# mgt_breakout.net
KiCad netlist of a schematic drawn in Altium Designer
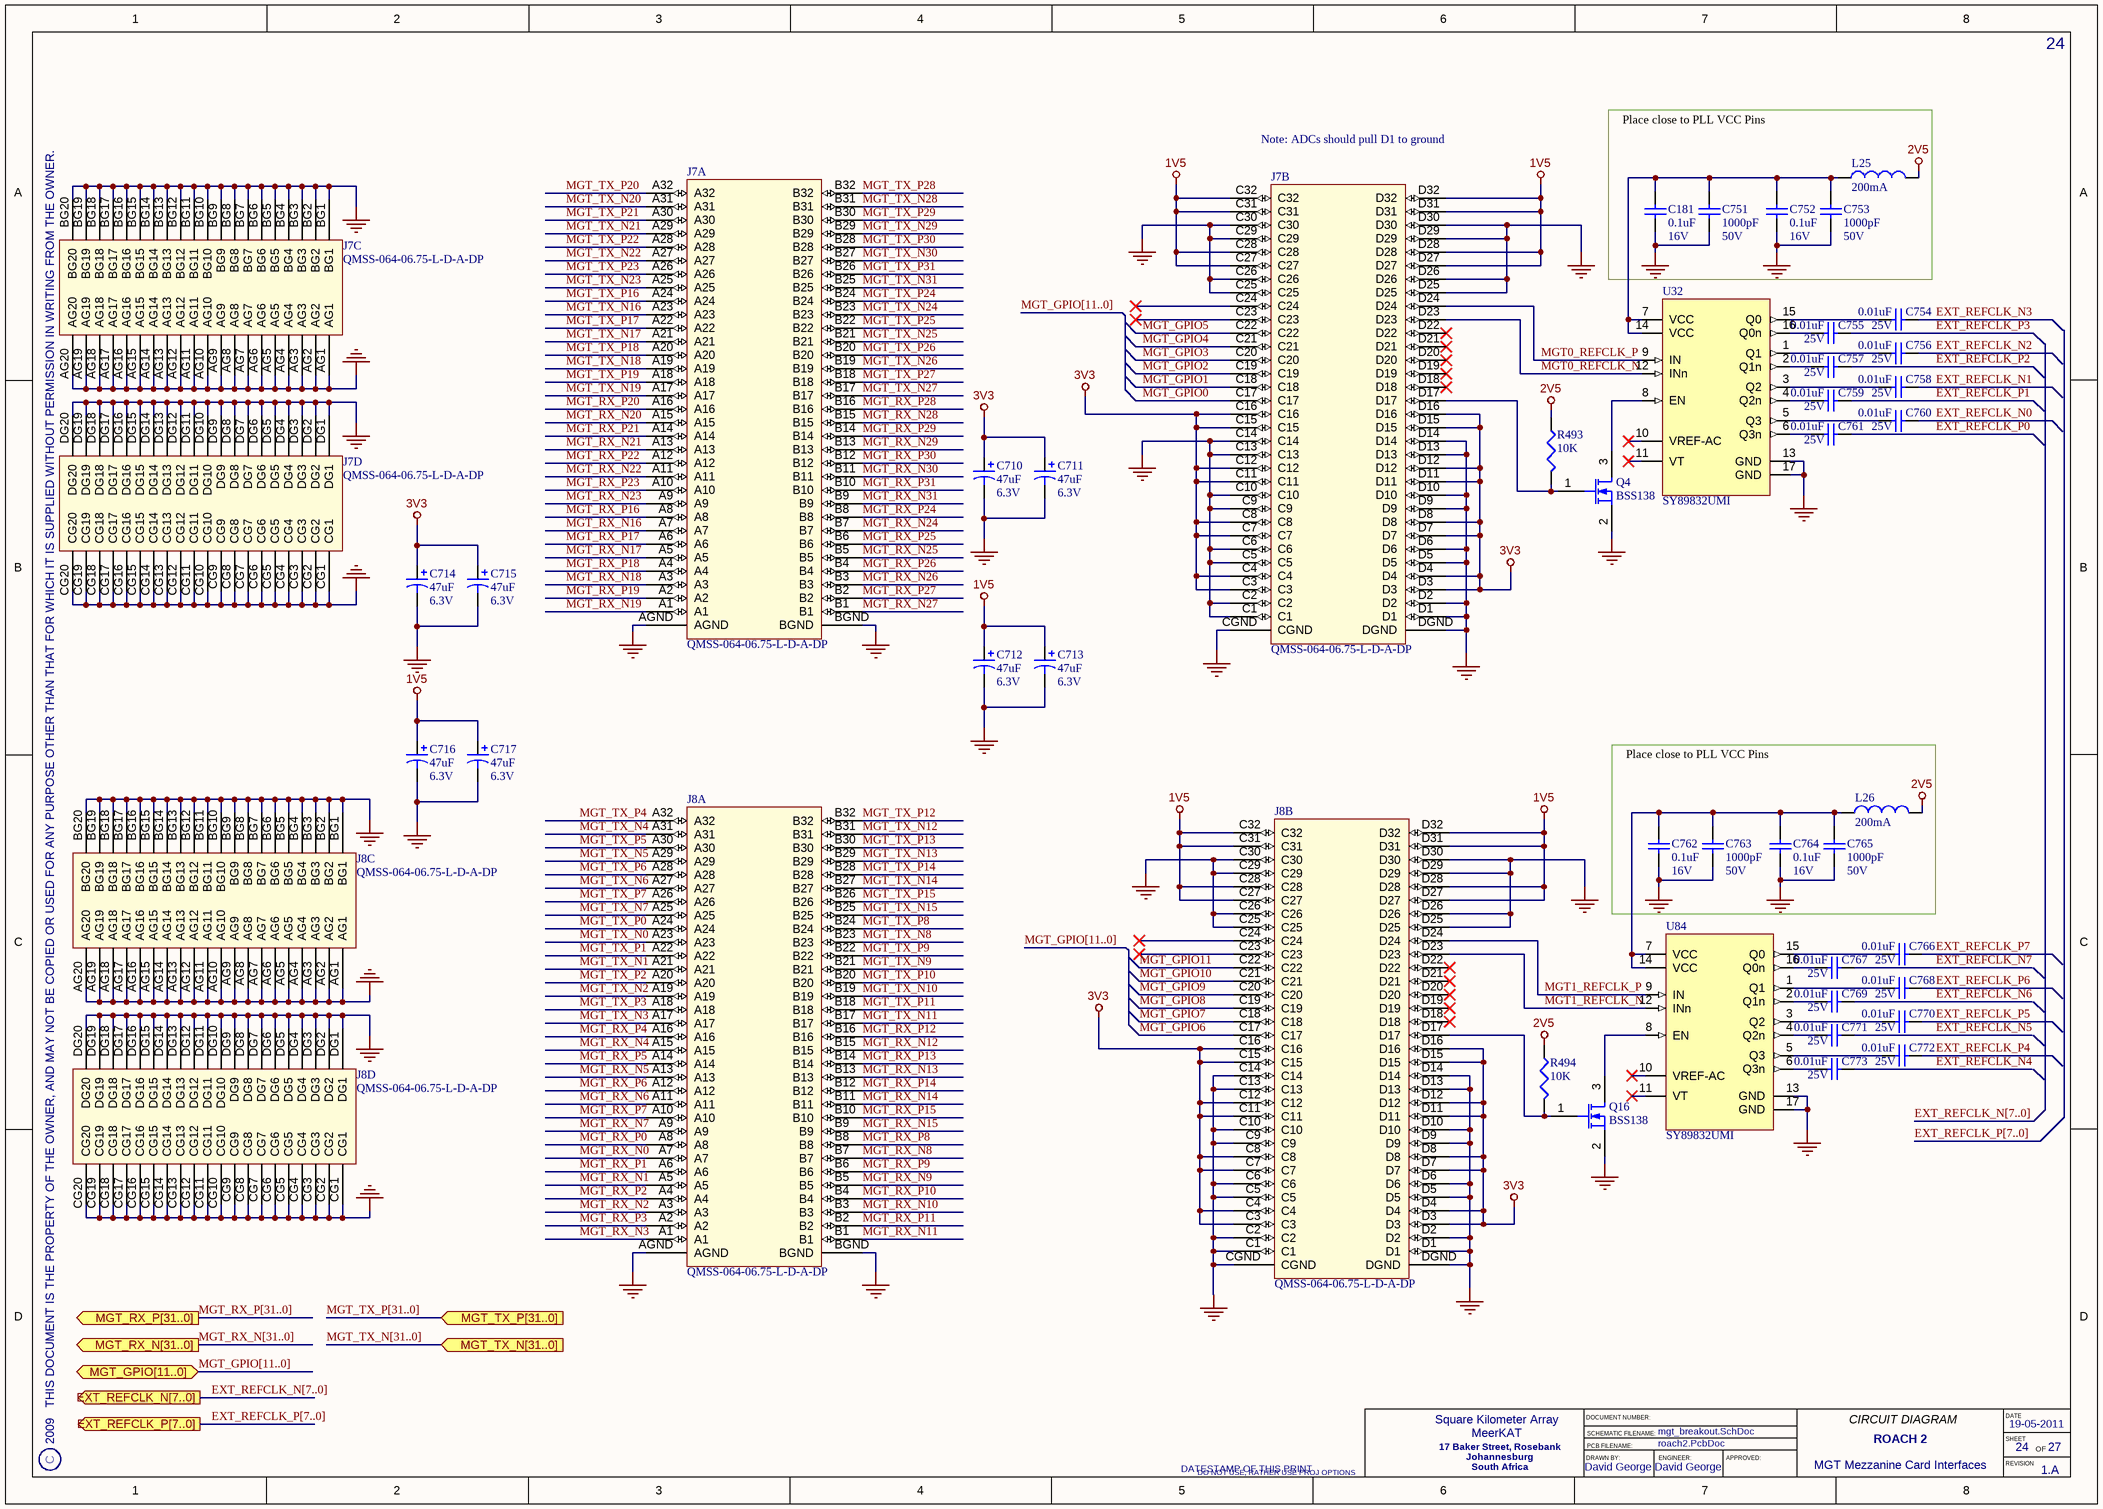
[diagram p0: mgt_breakout.SchDoc]

(export (version "E")
  (design (tool "Eeschema 10.0.6"))
  (components
    (comp (ref "C181")
      (value "0.1uF")
      (footprint "CAPC1005X60L")
      (description "0.1uF, Ceramic Capacitor")
      (fields
        (field (name "RATING") "16V")
        (field (name "MANUFACTURER") "VENKEL")
        (field (name "PARTNUM") "C0402X7R160-104KN")
      )
      (libsource (lib "altium_db") (part "CapStd"))
    )
    (comp (ref "C710")
      (value "47uF")
      (footprint "CAPMP3528X120L")
      (description "47uF, Conductive Polymer Chip Capacitor")
      (fields
        (field (name "RATING") "6.3V")
        (field (name "MANUFACTURER") "KEMET")
        (field (name "PARTNUM") "T520T476M006ATE070")
      )
      (libsource (lib "altium_db") (part "CapPol"))
    )
    (comp (ref "C711")
      (value "47uF")
      (footprint "CAPMP3528X120L")
      (description "47uF, Conductive Polymer Chip Capacitor")
      (fields
        (field (name "RATING") "6.3V")
        (field (name "MANUFACTURER") "KEMET")
        (field (name "PARTNUM") "T520T476M006ATE070")
      )
      (libsource (lib "altium_db") (part "CapPol"))
    )
    (comp (ref "C712")
      (value "47uF")
      (footprint "CAPMP3528X120L")
      (description "47uF, Conductive Polymer Chip Capacitor")
      (fields
        (field (name "RATING") "6.3V")
        (field (name "MANUFACTURER") "KEMET")
        (field (name "PARTNUM") "T520T476M006ATE070")
      )
      (libsource (lib "altium_db") (part "CapPol"))
    )
    (comp (ref "C713")
      (value "47uF")
      (footprint "CAPMP3528X120L")
      (description "47uF, Conductive Polymer Chip Capacitor")
      (fields
        (field (name "RATING") "6.3V")
        (field (name "MANUFACTURER") "KEMET")
        (field (name "PARTNUM") "T520T476M006ATE070")
      )
      (libsource (lib "altium_db") (part "CapPol"))
    )
    (comp (ref "C714")
      (value "47uF")
      (footprint "CAPMP3528X120L")
      (description "47uF, Conductive Polymer Chip Capacitor")
      (fields
        (field (name "RATING") "6.3V")
        (field (name "MANUFACTURER") "KEMET")
        (field (name "PARTNUM") "T520T476M006ATE070")
      )
      (libsource (lib "altium_db") (part "CapPol"))
    )
    (comp (ref "C715")
      (value "47uF")
      (footprint "CAPMP3528X120L")
      (description "47uF, Conductive Polymer Chip Capacitor")
      (fields
        (field (name "RATING") "6.3V")
        (field (name "MANUFACTURER") "KEMET")
        (field (name "PARTNUM") "T520T476M006ATE070")
      )
      (libsource (lib "altium_db") (part "CapPol"))
    )
    (comp (ref "C716")
      (value "47uF")
      (footprint "CAPMP3528X120L")
      (description "47uF, Conductive Polymer Chip Capacitor")
      (fields
        (field (name "RATING") "6.3V")
        (field (name "MANUFACTURER") "KEMET")
        (field (name "PARTNUM") "T520T476M006ATE070")
      )
      (libsource (lib "altium_db") (part "CapPol"))
    )
    (comp (ref "C717")
      (value "47uF")
      (footprint "CAPMP3528X120L")
      (description "47uF, Conductive Polymer Chip Capacitor")
      (fields
        (field (name "RATING") "6.3V")
        (field (name "MANUFACTURER") "KEMET")
        (field (name "PARTNUM") "T520T476M006ATE070")
      )
      (libsource (lib "altium_db") (part "CapPol"))
    )
    (comp (ref "C751")
      (value "1000pF")
      (footprint "CAPC1005X55L")
      (description "1000pF, Ceramic Capacitor")
      (fields
        (field (name "RATING") "50V")
        (field (name "MANUFACTURER") "MURATA")
        (field (name "PARTNUM") "GRM155R61H102KA01D")
      )
      (libsource (lib "altium_db") (part "CapStd"))
    )
    (comp (ref "C752")
      (value "0.1uF")
      (footprint "CAPC1005X60L")
      (description "0.1uF, Ceramic Capacitor")
      (fields
        (field (name "RATING") "16V")
        (field (name "MANUFACTURER") "VENKEL")
        (field (name "PARTNUM") "C0402X7R160-104KN")
      )
      (libsource (lib "altium_db") (part "CapStd"))
    )
    (comp (ref "C753")
      (value "1000pF")
      (footprint "CAPC1005X55L")
      (description "1000pF, Ceramic Capacitor")
      (fields
        (field (name "RATING") "50V")
        (field (name "MANUFACTURER") "MURATA")
        (field (name "PARTNUM") "GRM155R61H102KA01D")
      )
      (libsource (lib "altium_db") (part "CapStd"))
    )
    (comp (ref "C754")
      (value "0.01uF")
      (footprint "CAPC1005X55L")
      (description "0.01uF, Ceramic Capacitor")
      (fields
        (field (name "RATING") "25V")
        (field (name "MANUFACTURER") "MURATA")
        (field (name "PARTNUM") "GRM155R71E103KA01D")
      )
      (libsource (lib "altium_db") (part "CapStd"))
    )
    (comp (ref "C755")
      (value "0.01uF")
      (footprint "CAPC1005X55L")
      (description "0.01uF, Ceramic Capacitor")
      (fields
        (field (name "RATING") "25V")
        (field (name "MANUFACTURER") "MURATA")
        (field (name "PARTNUM") "GRM155R71E103KA01D")
      )
      (libsource (lib "altium_db") (part "CapStd"))
    )
    (comp (ref "C756")
      (value "0.01uF")
      (footprint "CAPC1005X55L")
      (description "0.01uF, Ceramic Capacitor")
      (fields
        (field (name "RATING") "25V")
        (field (name "MANUFACTURER") "MURATA")
        (field (name "PARTNUM") "GRM155R71E103KA01D")
      )
      (libsource (lib "altium_db") (part "CapStd"))
    )
    (comp (ref "C757")
      (value "0.01uF")
      (footprint "CAPC1005X55L")
      (description "0.01uF, Ceramic Capacitor")
      (fields
        (field (name "RATING") "25V")
        (field (name "MANUFACTURER") "MURATA")
        (field (name "PARTNUM") "GRM155R71E103KA01D")
      )
      (libsource (lib "altium_db") (part "CapStd"))
    )
    (comp (ref "C758")
      (value "0.01uF")
      (footprint "CAPC1005X55L")
      (description "0.01uF, Ceramic Capacitor")
      (fields
        (field (name "RATING") "25V")
        (field (name "MANUFACTURER") "MURATA")
        (field (name "PARTNUM") "GRM155R71E103KA01D")
      )
      (libsource (lib "altium_db") (part "CapStd"))
    )
    (comp (ref "C759")
      (value "0.01uF")
      (footprint "CAPC1005X55L")
      (description "0.01uF, Ceramic Capacitor")
      (fields
        (field (name "RATING") "25V")
        (field (name "MANUFACTURER") "MURATA")
        (field (name "PARTNUM") "GRM155R71E103KA01D")
      )
      (libsource (lib "altium_db") (part "CapStd"))
    )
    (comp (ref "C760")
      (value "0.01uF")
      (footprint "CAPC1005X55L")
      (description "0.01uF, Ceramic Capacitor")
      (fields
        (field (name "RATING") "25V")
        (field (name "MANUFACTURER") "MURATA")
        (field (name "PARTNUM") "GRM155R71E103KA01D")
      )
      (libsource (lib "altium_db") (part "CapStd"))
    )
    (comp (ref "C761")
      (value "0.01uF")
      (footprint "CAPC1005X55L")
      (description "0.01uF, Ceramic Capacitor")
      (fields
        (field (name "RATING") "25V")
        (field (name "MANUFACTURER") "MURATA")
        (field (name "PARTNUM") "GRM155R71E103KA01D")
      )
      (libsource (lib "altium_db") (part "CapStd"))
    )
    (comp (ref "C762")
      (value "0.1uF")
      (footprint "CAPC1005X60L")
      (description "0.1uF, Ceramic Capacitor")
      (fields
        (field (name "RATING") "16V")
        (field (name "MANUFACTURER") "VENKEL")
        (field (name "PARTNUM") "C0402X7R160-104KN")
      )
      (libsource (lib "altium_db") (part "CapStd"))
    )
    (comp (ref "C763")
      (value "1000pF")
      (footprint "CAPC1005X55L")
      (description "1000pF, Ceramic Capacitor")
      (fields
        (field (name "RATING") "50V")
        (field (name "MANUFACTURER") "MURATA")
        (field (name "PARTNUM") "GRM155R61H102KA01D")
      )
      (libsource (lib "altium_db") (part "CapStd"))
    )
    (comp (ref "C764")
      (value "0.1uF")
      (footprint "CAPC1005X60L")
      (description "0.1uF, Ceramic Capacitor")
      (fields
        (field (name "RATING") "16V")
        (field (name "MANUFACTURER") "VENKEL")
        (field (name "PARTNUM") "C0402X7R160-104KN")
      )
      (libsource (lib "altium_db") (part "CapStd"))
    )
    (comp (ref "C765")
      (value "1000pF")
      (footprint "CAPC1005X55L")
      (description "1000pF, Ceramic Capacitor")
      (fields
        (field (name "RATING") "50V")
        (field (name "MANUFACTURER") "MURATA")
        (field (name "PARTNUM") "GRM155R61H102KA01D")
      )
      (libsource (lib "altium_db") (part "CapStd"))
    )
    (comp (ref "C766")
      (value "0.01uF")
      (footprint "CAPC1005X55L")
      (description "0.01uF, Ceramic Capacitor")
      (fields
        (field (name "RATING") "25V")
        (field (name "MANUFACTURER") "MURATA")
        (field (name "PARTNUM") "GRM155R71E103KA01D")
      )
      (libsource (lib "altium_db") (part "CapStd"))
    )
    (comp (ref "C767")
      (value "0.01uF")
      (footprint "CAPC1005X55L")
      (description "0.01uF, Ceramic Capacitor")
      (fields
        (field (name "RATING") "25V")
        (field (name "MANUFACTURER") "MURATA")
        (field (name "PARTNUM") "GRM155R71E103KA01D")
      )
      (libsource (lib "altium_db") (part "CapStd"))
    )
    (comp (ref "C768")
      (value "0.01uF")
      (footprint "CAPC1005X55L")
      (description "0.01uF, Ceramic Capacitor")
      (fields
        (field (name "RATING") "25V")
        (field (name "MANUFACTURER") "MURATA")
        (field (name "PARTNUM") "GRM155R71E103KA01D")
      )
      (libsource (lib "altium_db") (part "CapStd"))
    )
    (comp (ref "C769")
      (value "0.01uF")
      (footprint "CAPC1005X55L")
      (description "0.01uF, Ceramic Capacitor")
      (fields
        (field (name "RATING") "25V")
        (field (name "MANUFACTURER") "MURATA")
        (field (name "PARTNUM") "GRM155R71E103KA01D")
      )
      (libsource (lib "altium_db") (part "CapStd"))
    )
    (comp (ref "C770")
      (value "0.01uF")
      (footprint "CAPC1005X55L")
      (description "0.01uF, Ceramic Capacitor")
      (fields
        (field (name "RATING") "25V")
        (field (name "MANUFACTURER") "MURATA")
        (field (name "PARTNUM") "GRM155R71E103KA01D")
      )
      (libsource (lib "altium_db") (part "CapStd"))
    )
    (comp (ref "C771")
      (value "0.01uF")
      (footprint "CAPC1005X55L")
      (description "0.01uF, Ceramic Capacitor")
      (fields
        (field (name "RATING") "25V")
        (field (name "MANUFACTURER") "MURATA")
        (field (name "PARTNUM") "GRM155R71E103KA01D")
      )
      (libsource (lib "altium_db") (part "CapStd"))
    )
    (comp (ref "C772")
      (value "0.01uF")
      (footprint "CAPC1005X55L")
      (description "0.01uF, Ceramic Capacitor")
      (fields
        (field (name "RATING") "25V")
        (field (name "MANUFACTURER") "MURATA")
        (field (name "PARTNUM") "GRM155R71E103KA01D")
      )
      (libsource (lib "altium_db") (part "CapStd"))
    )
    (comp (ref "C773")
      (value "0.01uF")
      (footprint "CAPC1005X55L")
      (description "0.01uF, Ceramic Capacitor")
      (fields
        (field (name "RATING") "25V")
        (field (name "MANUFACTURER") "MURATA")
        (field (name "PARTNUM") "GRM155R71E103KA01D")
      )
      (libsource (lib "altium_db") (part "CapStd"))
    )
    (comp (ref "J7")
      (value "QMSS-064-06_75-L-D-A-DP")
      (footprint "SAMTEC_QMSS-064-06_75-L-D-A-DP")
      (description "Shielded, 64-Differential Pair, Rugged High-Speed Terminal Strip, 0.635mm Pitch,")
      (fields (field (name "PARTNUM") "QMSS-064-06.75-L-D-A-DP"))
      (libsource (lib "altium_db") (part "QMSS-064-06_75-L-D-A-DP"))
    )
    (comp (ref "J8")
      (value "QMSS-064-06_75-L-D-A-DP")
      (footprint "SAMTEC_QMSS-064-06_75-L-D-A-DP")
      (description "Shielded, 64-Differential Pair, Rugged High-Speed Terminal Strip, 0.635mm Pitch,")
      (fields (field (name "PARTNUM") "QMSS-064-06.75-L-D-A-DP"))
      (libsource (lib "altium_db") (part "QMSS-064-06_75-L-D-A-DP"))
    )
    (comp (ref "L25")
      (value "600R")
      (footprint "INDC2012X130L")
      (description "600 Ohm, Chip Ferrite Bead")
      (fields
        (field (name "RATING") "200mA")
        (field (name "MANUFACTURER") "Murata")
        (field (name "PARTNUM") "BLM21BD601SN1")
      )
      (libsource (lib "altium_db") (part "IndStd"))
    )
    (comp (ref "L26")
      (value "600R")
      (footprint "INDC2012X130L")
      (description "600 Ohm, Chip Ferrite Bead")
      (fields
        (field (name "RATING") "200mA")
        (field (name "MANUFACTURER") "Murata")
        (field (name "PARTNUM") "BLM21BD601SN1")
      )
      (libsource (lib "altium_db") (part "IndStd"))
    )
    (comp (ref "Q4")
      (value "BSS138")
      (footprint "SOT95P245X110-3N")
      (description "N-Channel Logic Level Enhancement Mode Field Effect Transistor")
      (fields (field (name "MANUFACTURER") "Fairchild Semiconductor"))
      (libsource (lib "altium_db") (part "BSS138"))
    )
    (comp (ref "Q16")
      (value "BSS138")
      (footprint "SOT95P245X110-3N")
      (description "N-Channel Logic Level Enhancement Mode Field Effect Transistor")
      (fields (field (name "MANUFACTURER") "Fairchild Semiconductor"))
      (libsource (lib "altium_db") (part "BSS138"))
    )
    (comp (ref "R493")
      (value "10K")
      (footprint "RESC1005X40L")
      (description "10K, 1.1mm x 0.5mm, Thick Film Resistor")
      (fields (field (name "MANUFACTURER") "ROYALOHM") (field (name "PARTNUM") "0402WGJ0103T1E"))
      (libsource (lib "altium_db") (part "ResStd"))
    )
    (comp (ref "R494")
      (value "10K")
      (footprint "RESC1005X40L")
      (description "10K, 1.1mm x 0.5mm, Thick Film Resistor")
      (fields (field (name "MANUFACTURER") "ROYALOHM") (field (name "PARTNUM") "0402WGJ0103T1E"))
      (libsource (lib "altium_db") (part "ResStd"))
    )
    (comp (ref "U32")
      (value "SY89832UMI")
      (footprint "MLF-16")
      (description "2.5 C Ultra-precision 1:4 LVDS Fanout Buffer/Translator with Interal Termination")
      (fields (field (name "MANUFACTURER") "Micrel"))
      (libsource (lib "altium_db") (part "SY89832UMI"))
    )
    (comp (ref "U84")
      (value "SY89832UMI")
      (footprint "MLF-16")
      (description "2.5 C Ultra-precision 1:4 LVDS Fanout Buffer/Translator with Interal Termination")
      (fields (field (name "MANUFACTURER") "Micrel"))
      (libsource (lib "altium_db") (part "SY89832UMI"))
    )
  )
  (nets
    (net (code "1") (name "/EXT_REFCLK_N0") (class "Default")
      (node (ref "C760") (pin "2") (pinfunction "2_2") (pintype "passive"))
    )
    (net (code "2") (name "/EXT_REFCLK_N1") (class "Default")
      (node (ref "C758") (pin "2") (pinfunction "2_2") (pintype "passive"))
    )
    (net (code "3") (name "/EXT_REFCLK_N2") (class "Default")
      (node (ref "C756") (pin "2") (pinfunction "2_2") (pintype "passive"))
    )
    (net (code "4") (name "/EXT_REFCLK_N3") (class "Default")
      (node (ref "C754") (pin "2") (pinfunction "2_2") (pintype "passive"))
    )
    (net (code "5") (name "/EXT_REFCLK_N4") (class "Default")
      (node (ref "C773") (pin "2") (pinfunction "2_2") (pintype "passive"))
    )
    (net (code "6") (name "/EXT_REFCLK_N5") (class "Default")
      (node (ref "C771") (pin "2") (pinfunction "2_2") (pintype "passive"))
    )
    (net (code "7") (name "/EXT_REFCLK_N6") (class "Default")
      (node (ref "C769") (pin "2") (pinfunction "2_2") (pintype "passive"))
    )
    (net (code "8") (name "/EXT_REFCLK_N7") (class "Default")
      (node (ref "C767") (pin "2") (pinfunction "2_2") (pintype "passive"))
    )
    (net (code "10") (name "/EXT_REFCLK_P0") (class "Default")
      (node (ref "C761") (pin "2") (pinfunction "2_2") (pintype "passive"))
    )
    (net (code "11") (name "/EXT_REFCLK_P1") (class "Default")
      (node (ref "C759") (pin "2") (pinfunction "2_2") (pintype "passive"))
    )
    (net (code "12") (name "/EXT_REFCLK_P2") (class "Default")
      (node (ref "C757") (pin "2") (pinfunction "2_2") (pintype "passive"))
    )
    (net (code "13") (name "/EXT_REFCLK_P3") (class "Default")
      (node (ref "C755") (pin "2") (pinfunction "2_2") (pintype "passive"))
    )
    (net (code "14") (name "/EXT_REFCLK_P4") (class "Default")
      (node (ref "C772") (pin "2") (pinfunction "2_2") (pintype "passive"))
    )
    (net (code "15") (name "/EXT_REFCLK_P5") (class "Default")
      (node (ref "C770") (pin "2") (pinfunction "2_2") (pintype "passive"))
    )
    (net (code "16") (name "/EXT_REFCLK_P6") (class "Default")
      (node (ref "C768") (pin "2") (pinfunction "2_2") (pintype "passive"))
    )
    (net (code "17") (name "/EXT_REFCLK_P7") (class "Default")
      (node (ref "C766") (pin "2") (pinfunction "2_2") (pintype "passive"))
    )
    (net (code "19") (name "/MGT0_REFCLK_N") (class "Default")
      (node (ref "J7") (pin "D23") (pinfunction "D23_D23") (pintype "bidirectional"))
      (node (ref "U32") (pin "12") (pinfunction "INn_12") (pintype "input"))
    )
    (net (code "20") (name "/MGT0_REFCLK_P") (class "Default")
      (node (ref "J7") (pin "D24") (pinfunction "D24_D24") (pintype "bidirectional"))
      (node (ref "U32") (pin "9") (pinfunction "IN_9") (pintype "input"))
    )
    (net (code "21") (name "/MGT1_REFCLK_N") (class "Default")
      (node (ref "J8") (pin "D23") (pinfunction "D23_D23") (pintype "bidirectional"))
      (node (ref "U84") (pin "12") (pinfunction "INn_12") (pintype "input"))
    )
    (net (code "22") (name "/MGT1_REFCLK_P") (class "Default")
      (node (ref "J8") (pin "D24") (pinfunction "D24_D24") (pintype "bidirectional"))
      (node (ref "U84") (pin "9") (pinfunction "IN_9") (pintype "input"))
    )
    (net (code "23") (name "/MGT_GPIO0") (class "Default")
      (node (ref "J7") (pin "C17") (pinfunction "C17_C17") (pintype "bidirectional"))
    )
    (net (code "24") (name "/MGT_GPIO1") (class "Default")
      (node (ref "J7") (pin "C18") (pinfunction "C18_C18") (pintype "bidirectional"))
    )
    (net (code "25") (name "/MGT_GPIO2") (class "Default")
      (node (ref "J7") (pin "C19") (pinfunction "C19_C19") (pintype "bidirectional"))
    )
    (net (code "26") (name "/MGT_GPIO3") (class "Default")
      (node (ref "J7") (pin "C20") (pinfunction "C20_C20") (pintype "bidirectional"))
    )
    (net (code "27") (name "/MGT_GPIO4") (class "Default")
      (node (ref "J7") (pin "C21") (pinfunction "C21_C21") (pintype "bidirectional"))
    )
    (net (code "28") (name "/MGT_GPIO5") (class "Default")
      (node (ref "J7") (pin "C22") (pinfunction "C22_C22") (pintype "bidirectional"))
    )
    (net (code "29") (name "/MGT_GPIO6") (class "Default")
      (node (ref "J8") (pin "C17") (pinfunction "C17_C17") (pintype "bidirectional"))
    )
    (net (code "30") (name "/MGT_GPIO7") (class "Default")
      (node (ref "J8") (pin "C18") (pinfunction "C18_C18") (pintype "bidirectional"))
    )
    (net (code "31") (name "/MGT_GPIO8") (class "Default")
      (node (ref "J8") (pin "C19") (pinfunction "C19_C19") (pintype "bidirectional"))
    )
    (net (code "32") (name "/MGT_GPIO9") (class "Default")
      (node (ref "J8") (pin "C20") (pinfunction "C20_C20") (pintype "bidirectional"))
    )
    (net (code "33") (name "/MGT_GPIO10") (class "Default")
      (node (ref "J8") (pin "C21") (pinfunction "C21_C21") (pintype "bidirectional"))
    )
    (net (code "34") (name "/MGT_GPIO11") (class "Default")
      (node (ref "J8") (pin "C22") (pinfunction "C22_C22") (pintype "bidirectional"))
    )
    (net (code "36") (name "/MGT_RX_N0") (class "Default")
      (node (ref "J8") (pin "A7") (pinfunction "A7_A7") (pintype "bidirectional"))
    )
    (net (code "37") (name "/MGT_RX_N1") (class "Default")
      (node (ref "J8") (pin "A5") (pinfunction "A5_A5") (pintype "bidirectional"))
    )
    (net (code "38") (name "/MGT_RX_N2") (class "Default")
      (node (ref "J8") (pin "A3") (pinfunction "A3_A3") (pintype "bidirectional"))
    )
    (net (code "39") (name "/MGT_RX_N3") (class "Default")
      (node (ref "J8") (pin "A1") (pinfunction "A1_A1") (pintype "bidirectional"))
    )
    (net (code "40") (name "/MGT_RX_N4") (class "Default")
      (node (ref "J8") (pin "A15") (pinfunction "A15_A15") (pintype "bidirectional"))
    )
    (net (code "41") (name "/MGT_RX_N5") (class "Default")
      (node (ref "J8") (pin "A13") (pinfunction "A13_A13") (pintype "bidirectional"))
    )
    (net (code "42") (name "/MGT_RX_N6") (class "Default")
      (node (ref "J8") (pin "A11") (pinfunction "A11_A11") (pintype "bidirectional"))
    )
    (net (code "43") (name "/MGT_RX_N7") (class "Default")
      (node (ref "J8") (pin "A9") (pinfunction "A9_A9") (pintype "bidirectional"))
    )
    (net (code "44") (name "/MGT_RX_N8") (class "Default")
      (node (ref "J8") (pin "B7") (pinfunction "B7_B7") (pintype "bidirectional"))
    )
    (net (code "45") (name "/MGT_RX_N9") (class "Default")
      (node (ref "J8") (pin "B5") (pinfunction "B5_B5") (pintype "bidirectional"))
    )
    (net (code "46") (name "/MGT_RX_N10") (class "Default")
      (node (ref "J8") (pin "B3") (pinfunction "B3_B3") (pintype "bidirectional"))
    )
    (net (code "47") (name "/MGT_RX_N11") (class "Default")
      (node (ref "J8") (pin "B1") (pinfunction "B1_B1") (pintype "bidirectional"))
    )
    (net (code "48") (name "/MGT_RX_N12") (class "Default")
      (node (ref "J8") (pin "B15") (pinfunction "B15_B15") (pintype "bidirectional"))
    )
    (net (code "49") (name "/MGT_RX_N13") (class "Default")
      (node (ref "J8") (pin "B13") (pinfunction "B13_B13") (pintype "bidirectional"))
    )
    (net (code "50") (name "/MGT_RX_N14") (class "Default")
      (node (ref "J8") (pin "B11") (pinfunction "B11_B11") (pintype "bidirectional"))
    )
    (net (code "51") (name "/MGT_RX_N15") (class "Default")
      (node (ref "J8") (pin "B9") (pinfunction "B9_B9") (pintype "bidirectional"))
    )
    (net (code "52") (name "/MGT_RX_N16") (class "Default")
      (node (ref "J7") (pin "A7") (pinfunction "A7_A7") (pintype "bidirectional"))
    )
    (net (code "53") (name "/MGT_RX_N17") (class "Default")
      (node (ref "J7") (pin "A5") (pinfunction "A5_A5") (pintype "bidirectional"))
    )
    (net (code "54") (name "/MGT_RX_N18") (class "Default")
      (node (ref "J7") (pin "A3") (pinfunction "A3_A3") (pintype "bidirectional"))
    )
    (net (code "55") (name "/MGT_RX_N19") (class "Default")
      (node (ref "J7") (pin "A1") (pinfunction "A1_A1") (pintype "bidirectional"))
    )
    (net (code "56") (name "/MGT_RX_N20") (class "Default")
      (node (ref "J7") (pin "A15") (pinfunction "A15_A15") (pintype "bidirectional"))
    )
    (net (code "57") (name "/MGT_RX_N21") (class "Default")
      (node (ref "J7") (pin "A13") (pinfunction "A13_A13") (pintype "bidirectional"))
    )
    (net (code "58") (name "/MGT_RX_N22") (class "Default")
      (node (ref "J7") (pin "A11") (pinfunction "A11_A11") (pintype "bidirectional"))
    )
    (net (code "59") (name "/MGT_RX_N23") (class "Default")
      (node (ref "J7") (pin "A9") (pinfunction "A9_A9") (pintype "bidirectional"))
    )
    (net (code "60") (name "/MGT_RX_N24") (class "Default")
      (node (ref "J7") (pin "B7") (pinfunction "B7_B7") (pintype "bidirectional"))
    )
    (net (code "61") (name "/MGT_RX_N25") (class "Default")
      (node (ref "J7") (pin "B5") (pinfunction "B5_B5") (pintype "bidirectional"))
    )
    (net (code "62") (name "/MGT_RX_N26") (class "Default")
      (node (ref "J7") (pin "B3") (pinfunction "B3_B3") (pintype "bidirectional"))
    )
    (net (code "63") (name "/MGT_RX_N27") (class "Default")
      (node (ref "J7") (pin "B1") (pinfunction "B1_B1") (pintype "bidirectional"))
    )
    (net (code "64") (name "/MGT_RX_N28") (class "Default")
      (node (ref "J7") (pin "B15") (pinfunction "B15_B15") (pintype "bidirectional"))
    )
    (net (code "65") (name "/MGT_RX_N29") (class "Default")
      (node (ref "J7") (pin "B13") (pinfunction "B13_B13") (pintype "bidirectional"))
    )
    (net (code "66") (name "/MGT_RX_N30") (class "Default")
      (node (ref "J7") (pin "B11") (pinfunction "B11_B11") (pintype "bidirectional"))
    )
    (net (code "67") (name "/MGT_RX_N31") (class "Default")
      (node (ref "J7") (pin "B9") (pinfunction "B9_B9") (pintype "bidirectional"))
    )
    (net (code "69") (name "/MGT_RX_P0") (class "Default")
      (node (ref "J8") (pin "A8") (pinfunction "A8_A8") (pintype "bidirectional"))
    )
    (net (code "70") (name "/MGT_RX_P1") (class "Default")
      (node (ref "J8") (pin "A6") (pinfunction "A6_A6") (pintype "bidirectional"))
    )
    (net (code "71") (name "/MGT_RX_P2") (class "Default")
      (node (ref "J8") (pin "A4") (pinfunction "A4_A4") (pintype "bidirectional"))
    )
    (net (code "72") (name "/MGT_RX_P3") (class "Default")
      (node (ref "J8") (pin "A2") (pinfunction "A2_A2") (pintype "bidirectional"))
    )
    (net (code "73") (name "/MGT_RX_P4") (class "Default")
      (node (ref "J8") (pin "A16") (pinfunction "A16_A16") (pintype "bidirectional"))
    )
    (net (code "74") (name "/MGT_RX_P5") (class "Default")
      (node (ref "J8") (pin "A14") (pinfunction "A14_A14") (pintype "bidirectional"))
    )
    (net (code "75") (name "/MGT_RX_P6") (class "Default")
      (node (ref "J8") (pin "A12") (pinfunction "A12_A12") (pintype "bidirectional"))
    )
    (net (code "76") (name "/MGT_RX_P7") (class "Default")
      (node (ref "J8") (pin "A10") (pinfunction "A10_A10") (pintype "bidirectional"))
    )
    (net (code "77") (name "/MGT_RX_P8") (class "Default")
      (node (ref "J8") (pin "B8") (pinfunction "B8_B8") (pintype "bidirectional"))
    )
    (net (code "78") (name "/MGT_RX_P9") (class "Default")
      (node (ref "J8") (pin "B6") (pinfunction "B6_B6") (pintype "bidirectional"))
    )
    (net (code "79") (name "/MGT_RX_P10") (class "Default")
      (node (ref "J8") (pin "B4") (pinfunction "B4_B4") (pintype "bidirectional"))
    )
    (net (code "80") (name "/MGT_RX_P11") (class "Default")
      (node (ref "J8") (pin "B2") (pinfunction "B2_B2") (pintype "bidirectional"))
    )
    (net (code "81") (name "/MGT_RX_P12") (class "Default")
      (node (ref "J8") (pin "B16") (pinfunction "B16_B16") (pintype "bidirectional"))
    )
    (net (code "82") (name "/MGT_RX_P13") (class "Default")
      (node (ref "J8") (pin "B14") (pinfunction "B14_B14") (pintype "bidirectional"))
    )
    (net (code "83") (name "/MGT_RX_P14") (class "Default")
      (node (ref "J8") (pin "B12") (pinfunction "B12_B12") (pintype "bidirectional"))
    )
    (net (code "84") (name "/MGT_RX_P15") (class "Default")
      (node (ref "J8") (pin "B10") (pinfunction "B10_B10") (pintype "bidirectional"))
    )
    (net (code "85") (name "/MGT_RX_P16") (class "Default")
      (node (ref "J7") (pin "A8") (pinfunction "A8_A8") (pintype "bidirectional"))
    )
    (net (code "86") (name "/MGT_RX_P17") (class "Default")
      (node (ref "J7") (pin "A6") (pinfunction "A6_A6") (pintype "bidirectional"))
    )
    (net (code "87") (name "/MGT_RX_P18") (class "Default")
      (node (ref "J7") (pin "A4") (pinfunction "A4_A4") (pintype "bidirectional"))
    )
    (net (code "88") (name "/MGT_RX_P19") (class "Default")
      (node (ref "J7") (pin "A2") (pinfunction "A2_A2") (pintype "bidirectional"))
    )
    (net (code "89") (name "/MGT_RX_P20") (class "Default")
      (node (ref "J7") (pin "A16") (pinfunction "A16_A16") (pintype "bidirectional"))
    )
    (net (code "90") (name "/MGT_RX_P21") (class "Default")
      (node (ref "J7") (pin "A14") (pinfunction "A14_A14") (pintype "bidirectional"))
    )
    (net (code "91") (name "/MGT_RX_P22") (class "Default")
      (node (ref "J7") (pin "A12") (pinfunction "A12_A12") (pintype "bidirectional"))
    )
    (net (code "92") (name "/MGT_RX_P23") (class "Default")
      (node (ref "J7") (pin "A10") (pinfunction "A10_A10") (pintype "bidirectional"))
    )
    (net (code "93") (name "/MGT_RX_P24") (class "Default")
      (node (ref "J7") (pin "B8") (pinfunction "B8_B8") (pintype "bidirectional"))
    )
    (net (code "94") (name "/MGT_RX_P25") (class "Default")
      (node (ref "J7") (pin "B6") (pinfunction "B6_B6") (pintype "bidirectional"))
    )
    (net (code "95") (name "/MGT_RX_P26") (class "Default")
      (node (ref "J7") (pin "B4") (pinfunction "B4_B4") (pintype "bidirectional"))
    )
    (net (code "96") (name "/MGT_RX_P27") (class "Default")
      (node (ref "J7") (pin "B2") (pinfunction "B2_B2") (pintype "bidirectional"))
    )
    (net (code "97") (name "/MGT_RX_P28") (class "Default")
      (node (ref "J7") (pin "B16") (pinfunction "B16_B16") (pintype "bidirectional"))
    )
    (net (code "98") (name "/MGT_RX_P29") (class "Default")
      (node (ref "J7") (pin "B14") (pinfunction "B14_B14") (pintype "bidirectional"))
    )
    (net (code "99") (name "/MGT_RX_P30") (class "Default")
      (node (ref "J7") (pin "B12") (pinfunction "B12_B12") (pintype "bidirectional"))
    )
    (net (code "100") (name "/MGT_RX_P31") (class "Default")
      (node (ref "J7") (pin "B10") (pinfunction "B10_B10") (pintype "bidirectional"))
    )
    (net (code "102") (name "/MGT_TX_N0") (class "Default")
      (node (ref "J8") (pin "A23") (pinfunction "A23_A23") (pintype "bidirectional"))
    )
    (net (code "103") (name "/MGT_TX_N1") (class "Default")
      (node (ref "J8") (pin "A21") (pinfunction "A21_A21") (pintype "bidirectional"))
    )
    (net (code "104") (name "/MGT_TX_N2") (class "Default")
      (node (ref "J8") (pin "A19") (pinfunction "A19_A19") (pintype "bidirectional"))
    )
    (net (code "105") (name "/MGT_TX_N3") (class "Default")
      (node (ref "J8") (pin "A17") (pinfunction "A17_A17") (pintype "bidirectional"))
    )
    (net (code "106") (name "/MGT_TX_N4") (class "Default")
      (node (ref "J8") (pin "A31") (pinfunction "A31_A31") (pintype "bidirectional"))
    )
    (net (code "107") (name "/MGT_TX_N5") (class "Default")
      (node (ref "J8") (pin "A29") (pinfunction "A29_A29") (pintype "bidirectional"))
    )
    (net (code "108") (name "/MGT_TX_N6") (class "Default")
      (node (ref "J8") (pin "A27") (pinfunction "A27_A27") (pintype "bidirectional"))
    )
    (net (code "109") (name "/MGT_TX_N7") (class "Default")
      (node (ref "J8") (pin "A25") (pinfunction "A25_A25") (pintype "bidirectional"))
    )
    (net (code "110") (name "/MGT_TX_N8") (class "Default")
      (node (ref "J8") (pin "B23") (pinfunction "B23_B23") (pintype "bidirectional"))
    )
    (net (code "111") (name "/MGT_TX_N9") (class "Default")
      (node (ref "J8") (pin "B21") (pinfunction "B21_B21") (pintype "bidirectional"))
    )
    (net (code "112") (name "/MGT_TX_N10") (class "Default")
      (node (ref "J8") (pin "B19") (pinfunction "B19_B19") (pintype "bidirectional"))
    )
    (net (code "113") (name "/MGT_TX_N11") (class "Default")
      (node (ref "J8") (pin "B17") (pinfunction "B17_B17") (pintype "bidirectional"))
    )
    (net (code "114") (name "/MGT_TX_N12") (class "Default")
      (node (ref "J8") (pin "B31") (pinfunction "B31_B31") (pintype "bidirectional"))
    )
    (net (code "115") (name "/MGT_TX_N13") (class "Default")
      (node (ref "J8") (pin "B29") (pinfunction "B29_B29") (pintype "bidirectional"))
    )
    (net (code "116") (name "/MGT_TX_N14") (class "Default")
      (node (ref "J8") (pin "B27") (pinfunction "B27_B27") (pintype "bidirectional"))
    )
    (net (code "117") (name "/MGT_TX_N15") (class "Default")
      (node (ref "J8") (pin "B25") (pinfunction "B25_B25") (pintype "bidirectional"))
    )
    (net (code "118") (name "/MGT_TX_N16") (class "Default")
      (node (ref "J7") (pin "A23") (pinfunction "A23_A23") (pintype "bidirectional"))
    )
    (net (code "119") (name "/MGT_TX_N17") (class "Default")
      (node (ref "J7") (pin "A21") (pinfunction "A21_A21") (pintype "bidirectional"))
    )
    (net (code "120") (name "/MGT_TX_N18") (class "Default")
      (node (ref "J7") (pin "A19") (pinfunction "A19_A19") (pintype "bidirectional"))
    )
    (net (code "121") (name "/MGT_TX_N19") (class "Default")
      (node (ref "J7") (pin "A17") (pinfunction "A17_A17") (pintype "bidirectional"))
    )
    (net (code "122") (name "/MGT_TX_N20") (class "Default")
      (node (ref "J7") (pin "A31") (pinfunction "A31_A31") (pintype "bidirectional"))
    )
    (net (code "123") (name "/MGT_TX_N21") (class "Default")
      (node (ref "J7") (pin "A29") (pinfunction "A29_A29") (pintype "bidirectional"))
    )
    (net (code "124") (name "/MGT_TX_N22") (class "Default")
      (node (ref "J7") (pin "A27") (pinfunction "A27_A27") (pintype "bidirectional"))
    )
    (net (code "125") (name "/MGT_TX_N23") (class "Default")
      (node (ref "J7") (pin "A25") (pinfunction "A25_A25") (pintype "bidirectional"))
    )
    (net (code "126") (name "/MGT_TX_N24") (class "Default")
      (node (ref "J7") (pin "B23") (pinfunction "B23_B23") (pintype "bidirectional"))
    )
    (net (code "127") (name "/MGT_TX_N25") (class "Default")
      (node (ref "J7") (pin "B21") (pinfunction "B21_B21") (pintype "bidirectional"))
    )
    (net (code "128") (name "/MGT_TX_N26") (class "Default")
      (node (ref "J7") (pin "B19") (pinfunction "B19_B19") (pintype "bidirectional"))
    )
    (net (code "129") (name "/MGT_TX_N27") (class "Default")
      (node (ref "J7") (pin "B17") (pinfunction "B17_B17") (pintype "bidirectional"))
    )
    (net (code "130") (name "/MGT_TX_N28") (class "Default")
      (node (ref "J7") (pin "B31") (pinfunction "B31_B31") (pintype "bidirectional"))
    )
    (net (code "131") (name "/MGT_TX_N29") (class "Default")
      (node (ref "J7") (pin "B29") (pinfunction "B29_B29") (pintype "bidirectional"))
    )
    (net (code "132") (name "/MGT_TX_N30") (class "Default")
      (node (ref "J7") (pin "B27") (pinfunction "B27_B27") (pintype "bidirectional"))
    )
    (net (code "133") (name "/MGT_TX_N31") (class "Default")
      (node (ref "J7") (pin "B25") (pinfunction "B25_B25") (pintype "bidirectional"))
    )
    (net (code "135") (name "/MGT_TX_P0") (class "Default")
      (node (ref "J8") (pin "A24") (pinfunction "A24_A24") (pintype "bidirectional"))
    )
    (net (code "136") (name "/MGT_TX_P1") (class "Default")
      (node (ref "J8") (pin "A22") (pinfunction "A22_A22") (pintype "bidirectional"))
    )
    (net (code "137") (name "/MGT_TX_P2") (class "Default")
      (node (ref "J8") (pin "A20") (pinfunction "A20_A20") (pintype "bidirectional"))
    )
    (net (code "138") (name "/MGT_TX_P3") (class "Default")
      (node (ref "J8") (pin "A18") (pinfunction "A18_A18") (pintype "bidirectional"))
    )
    (net (code "139") (name "/MGT_TX_P4") (class "Default")
      (node (ref "J8") (pin "A32") (pinfunction "A32_A32") (pintype "bidirectional"))
    )
    (net (code "140") (name "/MGT_TX_P5") (class "Default")
      (node (ref "J8") (pin "A30") (pinfunction "A30_A30") (pintype "bidirectional"))
    )
    (net (code "141") (name "/MGT_TX_P6") (class "Default")
      (node (ref "J8") (pin "A28") (pinfunction "A28_A28") (pintype "bidirectional"))
    )
    (net (code "142") (name "/MGT_TX_P7") (class "Default")
      (node (ref "J8") (pin "A26") (pinfunction "A26_A26") (pintype "bidirectional"))
    )
    (net (code "143") (name "/MGT_TX_P8") (class "Default")
      (node (ref "J8") (pin "B24") (pinfunction "B24_B24") (pintype "bidirectional"))
    )
    (net (code "144") (name "/MGT_TX_P9") (class "Default")
      (node (ref "J8") (pin "B22") (pinfunction "B22_B22") (pintype "bidirectional"))
    )
    (net (code "145") (name "/MGT_TX_P10") (class "Default")
      (node (ref "J8") (pin "B20") (pinfunction "B20_B20") (pintype "bidirectional"))
    )
    (net (code "146") (name "/MGT_TX_P11") (class "Default")
      (node (ref "J8") (pin "B18") (pinfunction "B18_B18") (pintype "bidirectional"))
    )
    (net (code "147") (name "/MGT_TX_P12") (class "Default")
      (node (ref "J8") (pin "B32") (pinfunction "B32_B32") (pintype "bidirectional"))
    )
    (net (code "148") (name "/MGT_TX_P13") (class "Default")
      (node (ref "J8") (pin "B30") (pinfunction "B30_B30") (pintype "bidirectional"))
    )
    (net (code "149") (name "/MGT_TX_P14") (class "Default")
      (node (ref "J8") (pin "B28") (pinfunction "B28_B28") (pintype "bidirectional"))
    )
    (net (code "150") (name "/MGT_TX_P15") (class "Default")
      (node (ref "J8") (pin "B26") (pinfunction "B26_B26") (pintype "bidirectional"))
    )
    (net (code "151") (name "/MGT_TX_P16") (class "Default")
      (node (ref "J7") (pin "A24") (pinfunction "A24_A24") (pintype "bidirectional"))
    )
    (net (code "152") (name "/MGT_TX_P17") (class "Default")
      (node (ref "J7") (pin "A22") (pinfunction "A22_A22") (pintype "bidirectional"))
    )
    (net (code "153") (name "/MGT_TX_P18") (class "Default")
      (node (ref "J7") (pin "A20") (pinfunction "A20_A20") (pintype "bidirectional"))
    )
    (net (code "154") (name "/MGT_TX_P19") (class "Default")
      (node (ref "J7") (pin "A18") (pinfunction "A18_A18") (pintype "bidirectional"))
    )
    (net (code "155") (name "/MGT_TX_P20") (class "Default")
      (node (ref "J7") (pin "A32") (pinfunction "A32_A32") (pintype "bidirectional"))
    )
    (net (code "156") (name "/MGT_TX_P21") (class "Default")
      (node (ref "J7") (pin "A30") (pinfunction "A30_A30") (pintype "bidirectional"))
    )
    (net (code "157") (name "/MGT_TX_P22") (class "Default")
      (node (ref "J7") (pin "A28") (pinfunction "A28_A28") (pintype "bidirectional"))
    )
    (net (code "158") (name "/MGT_TX_P23") (class "Default")
      (node (ref "J7") (pin "A26") (pinfunction "A26_A26") (pintype "bidirectional"))
    )
    (net (code "159") (name "/MGT_TX_P24") (class "Default")
      (node (ref "J7") (pin "B24") (pinfunction "B24_B24") (pintype "bidirectional"))
    )
    (net (code "160") (name "/MGT_TX_P25") (class "Default")
      (node (ref "J7") (pin "B22") (pinfunction "B22_B22") (pintype "bidirectional"))
    )
    (net (code "161") (name "/MGT_TX_P26") (class "Default")
      (node (ref "J7") (pin "B20") (pinfunction "B20_B20") (pintype "bidirectional"))
    )
    (net (code "162") (name "/MGT_TX_P27") (class "Default")
      (node (ref "J7") (pin "B18") (pinfunction "B18_B18") (pintype "bidirectional"))
    )
    (net (code "163") (name "/MGT_TX_P28") (class "Default")
      (node (ref "J7") (pin "B32") (pinfunction "B32_B32") (pintype "bidirectional"))
    )
    (net (code "164") (name "/MGT_TX_P29") (class "Default")
      (node (ref "J7") (pin "B30") (pinfunction "B30_B30") (pintype "bidirectional"))
    )
    (net (code "165") (name "/MGT_TX_P30") (class "Default")
      (node (ref "J7") (pin "B28") (pinfunction "B28_B28") (pintype "bidirectional"))
    )
    (net (code "166") (name "/MGT_TX_P31") (class "Default")
      (node (ref "J7") (pin "B26") (pinfunction "B26_B26") (pintype "bidirectional"))
    )
    (net (code "168") (name "1V5") (class "Default")
      (node (ref "C712") (pin "1") (pinfunction "1_1") (pintype "passive"))
      (node (ref "C713") (pin "1") (pinfunction "1_1") (pintype "passive"))
      (node (ref "C716") (pin "1") (pinfunction "1_1") (pintype "passive"))
      (node (ref "C717") (pin "1") (pinfunction "1_1") (pintype "passive"))
      (node (ref "J7") (pin "C27") (pinfunction "C27_C27") (pintype "bidirectional"))
      (node (ref "J7") (pin "C28") (pinfunction "C28_C28") (pintype "bidirectional"))
      (node (ref "J7") (pin "C31") (pinfunction "C31_C31") (pintype "bidirectional"))
      (node (ref "J7") (pin "C32") (pinfunction "C32_C32") (pintype "bidirectional"))
      (node (ref "J7") (pin "D27") (pinfunction "D27_D27") (pintype "bidirectional"))
      (node (ref "J7") (pin "D28") (pinfunction "D28_D28") (pintype "bidirectional"))
      (node (ref "J7") (pin "D31") (pinfunction "D31_D31") (pintype "bidirectional"))
      (node (ref "J7") (pin "D32") (pinfunction "D32_D32") (pintype "bidirectional"))
      (node (ref "J8") (pin "C27") (pinfunction "C27_C27") (pintype "bidirectional"))
      (node (ref "J8") (pin "C28") (pinfunction "C28_C28") (pintype "bidirectional"))
      (node (ref "J8") (pin "C31") (pinfunction "C31_C31") (pintype "bidirectional"))
      (node (ref "J8") (pin "C32") (pinfunction "C32_C32") (pintype "bidirectional"))
      (node (ref "J8") (pin "D27") (pinfunction "D27_D27") (pintype "bidirectional"))
      (node (ref "J8") (pin "D28") (pinfunction "D28_D28") (pintype "bidirectional"))
      (node (ref "J8") (pin "D31") (pinfunction "D31_D31") (pintype "bidirectional"))
      (node (ref "J8") (pin "D32") (pinfunction "D32_D32") (pintype "bidirectional"))
    )
    (net (code "169") (name "2V5") (class "Default")
      (node (ref "L25") (pin "2") (pinfunction "2_2") (pintype "passive"))
      (node (ref "L26") (pin "2") (pinfunction "2_2") (pintype "passive"))
      (node (ref "R493") (pin "1") (pinfunction "1_1") (pintype "passive"))
      (node (ref "R494") (pin "1") (pinfunction "1_1") (pintype "passive"))
    )
    (net (code "170") (name "3V3") (class "Default")
      (node (ref "C710") (pin "1") (pinfunction "1_1") (pintype "passive"))
      (node (ref "C711") (pin "1") (pinfunction "1_1") (pintype "passive"))
      (node (ref "C714") (pin "1") (pinfunction "1_1") (pintype "passive"))
      (node (ref "C715") (pin "1") (pinfunction "1_1") (pintype "passive"))
      (node (ref "J7") (pin "C11") (pinfunction "C11_C11") (pintype "bidirectional"))
      (node (ref "J7") (pin "C12") (pinfunction "C12_C12") (pintype "bidirectional"))
      (node (ref "J7") (pin "C15") (pinfunction "C15_C15") (pintype "bidirectional"))
      (node (ref "J7") (pin "C16") (pinfunction "C16_C16") (pintype "bidirectional"))
      (node (ref "J7") (pin "C3") (pinfunction "C3_C3") (pintype "bidirectional"))
      (node (ref "J7") (pin "C4") (pinfunction "C4_C4") (pintype "bidirectional"))
      (node (ref "J7") (pin "C7") (pinfunction "C7_C7") (pintype "bidirectional"))
      (node (ref "J7") (pin "C8") (pinfunction "C8_C8") (pintype "bidirectional"))
      (node (ref "J7") (pin "D11") (pinfunction "D11_D11") (pintype "bidirectional"))
      (node (ref "J7") (pin "D12") (pinfunction "D12_D12") (pintype "bidirectional"))
      (node (ref "J7") (pin "D15") (pinfunction "D15_D15") (pintype "bidirectional"))
      (node (ref "J7") (pin "D16") (pinfunction "D16_D16") (pintype "bidirectional"))
      (node (ref "J7") (pin "D3") (pinfunction "D3_D3") (pintype "bidirectional"))
      (node (ref "J7") (pin "D4") (pinfunction "D4_D4") (pintype "bidirectional"))
      (node (ref "J7") (pin "D7") (pinfunction "D7_D7") (pintype "bidirectional"))
      (node (ref "J7") (pin "D8") (pinfunction "D8_D8") (pintype "bidirectional"))
      (node (ref "J8") (pin "C11") (pinfunction "C11_C11") (pintype "bidirectional"))
      (node (ref "J8") (pin "C12") (pinfunction "C12_C12") (pintype "bidirectional"))
      (node (ref "J8") (pin "C15") (pinfunction "C15_C15") (pintype "bidirectional"))
      (node (ref "J8") (pin "C16") (pinfunction "C16_C16") (pintype "bidirectional"))
      (node (ref "J8") (pin "C3") (pinfunction "C3_C3") (pintype "bidirectional"))
      (node (ref "J8") (pin "C4") (pinfunction "C4_C4") (pintype "bidirectional"))
      (node (ref "J8") (pin "C7") (pinfunction "C7_C7") (pintype "bidirectional"))
      (node (ref "J8") (pin "C8") (pinfunction "C8_C8") (pintype "bidirectional"))
      (node (ref "J8") (pin "D11") (pinfunction "D11_D11") (pintype "bidirectional"))
      (node (ref "J8") (pin "D12") (pinfunction "D12_D12") (pintype "bidirectional"))
      (node (ref "J8") (pin "D15") (pinfunction "D15_D15") (pintype "bidirectional"))
      (node (ref "J8") (pin "D16") (pinfunction "D16_D16") (pintype "bidirectional"))
      (node (ref "J8") (pin "D3") (pinfunction "D3_D3") (pintype "bidirectional"))
      (node (ref "J8") (pin "D4") (pinfunction "D4_D4") (pintype "bidirectional"))
      (node (ref "J8") (pin "D7") (pinfunction "D7_D7") (pintype "bidirectional"))
      (node (ref "J8") (pin "D8") (pinfunction "D8_D8") (pintype "bidirectional"))
    )
    (net (code "171") (name "GND") (class "Default")
      (node (ref "C181") (pin "1") (pinfunction "1_1") (pintype "passive"))
      (node (ref "C710") (pin "2") (pinfunction "2_2") (pintype "passive"))
      (node (ref "C711") (pin "2") (pinfunction "2_2") (pintype "passive"))
      (node (ref "C712") (pin "2") (pinfunction "2_2") (pintype "passive"))
      (node (ref "C713") (pin "2") (pinfunction "2_2") (pintype "passive"))
      (node (ref "C714") (pin "2") (pinfunction "2_2") (pintype "passive"))
      (node (ref "C715") (pin "2") (pinfunction "2_2") (pintype "passive"))
      (node (ref "C716") (pin "2") (pinfunction "2_2") (pintype "passive"))
      (node (ref "C717") (pin "2") (pinfunction "2_2") (pintype "passive"))
      (node (ref "C751") (pin "1") (pinfunction "1_1") (pintype "passive"))
      (node (ref "C752") (pin "1") (pinfunction "1_1") (pintype "passive"))
      (node (ref "C753") (pin "1") (pinfunction "1_1") (pintype "passive"))
      (node (ref "C762") (pin "1") (pinfunction "1_1") (pintype "passive"))
      (node (ref "C763") (pin "1") (pinfunction "1_1") (pintype "passive"))
      (node (ref "C764") (pin "1") (pinfunction "1_1") (pintype "passive"))
      (node (ref "C765") (pin "1") (pinfunction "1_1") (pintype "passive"))
      (node (ref "J7") (pin "AG1") (pinfunction "AG1_AG1") (pintype "power_in"))
      (node (ref "J7") (pin "AG10") (pinfunction "AG10_AG10") (pintype "power_in"))
      (node (ref "J7") (pin "AG11") (pinfunction "AG11_AG11") (pintype "power_in"))
      (node (ref "J7") (pin "AG12") (pinfunction "AG12_AG12") (pintype "power_in"))
      (node (ref "J7") (pin "AG13") (pinfunction "AG13_AG13") (pintype "power_in"))
      (node (ref "J7") (pin "AG14") (pinfunction "AG14_AG14") (pintype "power_in"))
      (node (ref "J7") (pin "AG15") (pinfunction "AG15_AG15") (pintype "power_in"))
      (node (ref "J7") (pin "AG16") (pinfunction "AG16_AG16") (pintype "power_in"))
      (node (ref "J7") (pin "AG17") (pinfunction "AG17_AG17") (pintype "power_in"))
      (node (ref "J7") (pin "AG18") (pinfunction "AG18_AG18") (pintype "power_in"))
      (node (ref "J7") (pin "AG19") (pinfunction "AG19_AG19") (pintype "power_in"))
      (node (ref "J7") (pin "AG2") (pinfunction "AG2_AG2") (pintype "power_in"))
      (node (ref "J7") (pin "AG20") (pinfunction "AG20_AG20") (pintype "power_in"))
      (node (ref "J7") (pin "AG3") (pinfunction "AG3_AG3") (pintype "power_in"))
      (node (ref "J7") (pin "AG4") (pinfunction "AG4_AG4") (pintype "power_in"))
      (node (ref "J7") (pin "AG5") (pinfunction "AG5_AG5") (pintype "power_in"))
      (node (ref "J7") (pin "AG6") (pinfunction "AG6_AG6") (pintype "power_in"))
      (node (ref "J7") (pin "AG7") (pinfunction "AG7_AG7") (pintype "power_in"))
      (node (ref "J7") (pin "AG8") (pinfunction "AG8_AG8") (pintype "power_in"))
      (node (ref "J7") (pin "AG9") (pinfunction "AG9_AG9") (pintype "power_in"))
      (node (ref "J7") (pin "AGND") (pinfunction "AGND_AGND") (pintype "power_in"))
      (node (ref "J7") (pin "BG1") (pinfunction "BG1_BG1") (pintype "power_in"))
      (node (ref "J7") (pin "BG10") (pinfunction "BG10_BG10") (pintype "power_in"))
      (node (ref "J7") (pin "BG11") (pinfunction "BG11_BG11") (pintype "power_in"))
      (node (ref "J7") (pin "BG12") (pinfunction "BG12_BG12") (pintype "power_in"))
      (node (ref "J7") (pin "BG13") (pinfunction "BG13_BG13") (pintype "power_in"))
      (node (ref "J7") (pin "BG14") (pinfunction "BG14_BG14") (pintype "power_in"))
      (node (ref "J7") (pin "BG15") (pinfunction "BG15_BG15") (pintype "power_in"))
      (node (ref "J7") (pin "BG16") (pinfunction "BG16_BG16") (pintype "power_in"))
      (node (ref "J7") (pin "BG17") (pinfunction "BG17_BG17") (pintype "power_in"))
      (node (ref "J7") (pin "BG18") (pinfunction "BG18_BG18") (pintype "power_in"))
      (node (ref "J7") (pin "BG19") (pinfunction "BG19_BG19") (pintype "power_in"))
      (node (ref "J7") (pin "BG2") (pinfunction "BG2_BG2") (pintype "power_in"))
      (node (ref "J7") (pin "BG20") (pinfunction "BG20_BG20") (pintype "power_in"))
      (node (ref "J7") (pin "BG3") (pinfunction "BG3_BG3") (pintype "power_in"))
      (node (ref "J7") (pin "BG4") (pinfunction "BG4_BG4") (pintype "power_in"))
      (node (ref "J7") (pin "BG5") (pinfunction "BG5_BG5") (pintype "power_in"))
      (node (ref "J7") (pin "BG6") (pinfunction "BG6_BG6") (pintype "power_in"))
      (node (ref "J7") (pin "BG7") (pinfunction "BG7_BG7") (pintype "power_in"))
      (node (ref "J7") (pin "BG8") (pinfunction "BG8_BG8") (pintype "power_in"))
      (node (ref "J7") (pin "BG9") (pinfunction "BG9_BG9") (pintype "power_in"))
      (node (ref "J7") (pin "BGND") (pinfunction "BGND_BGND") (pintype "power_in"))
      (node (ref "J7") (pin "C1") (pinfunction "C1_C1") (pintype "bidirectional"))
      (node (ref "J7") (pin "C10") (pinfunction "C10_C10") (pintype "bidirectional"))
      (node (ref "J7") (pin "C13") (pinfunction "C13_C13") (pintype "bidirectional"))
      (node (ref "J7") (pin "C14") (pinfunction "C14_C14") (pintype "bidirectional"))
      (node (ref "J7") (pin "C2") (pinfunction "C2_C2") (pintype "bidirectional"))
      (node (ref "J7") (pin "C25") (pinfunction "C25_C25") (pintype "bidirectional"))
      (node (ref "J7") (pin "C26") (pinfunction "C26_C26") (pintype "bidirectional"))
      (node (ref "J7") (pin "C29") (pinfunction "C29_C29") (pintype "bidirectional"))
      (node (ref "J7") (pin "C30") (pinfunction "C30_C30") (pintype "bidirectional"))
      (node (ref "J7") (pin "C5") (pinfunction "C5_C5") (pintype "bidirectional"))
      (node (ref "J7") (pin "C6") (pinfunction "C6_C6") (pintype "bidirectional"))
      (node (ref "J7") (pin "C9") (pinfunction "C9_C9") (pintype "bidirectional"))
      (node (ref "J7") (pin "CG1") (pinfunction "CG1_CG1") (pintype "power_in"))
      (node (ref "J7") (pin "CG10") (pinfunction "CG10_CG10") (pintype "power_in"))
      (node (ref "J7") (pin "CG11") (pinfunction "CG11_CG11") (pintype "power_in"))
      (node (ref "J7") (pin "CG12") (pinfunction "CG12_CG12") (pintype "power_in"))
      (node (ref "J7") (pin "CG13") (pinfunction "CG13_CG13") (pintype "power_in"))
      (node (ref "J7") (pin "CG14") (pinfunction "CG14_CG14") (pintype "power_in"))
      (node (ref "J7") (pin "CG15") (pinfunction "CG15_CG15") (pintype "power_in"))
      (node (ref "J7") (pin "CG16") (pinfunction "CG16_CG16") (pintype "power_in"))
      (node (ref "J7") (pin "CG17") (pinfunction "CG17_CG17") (pintype "power_in"))
      (node (ref "J7") (pin "CG18") (pinfunction "CG18_CG18") (pintype "power_in"))
      (node (ref "J7") (pin "CG19") (pinfunction "CG19_CG19") (pintype "power_in"))
      (node (ref "J7") (pin "CG2") (pinfunction "CG2_CG2") (pintype "power_in"))
      (node (ref "J7") (pin "CG20") (pinfunction "CG20_CG20") (pintype "power_in"))
      (node (ref "J7") (pin "CG3") (pinfunction "CG3_CG3") (pintype "power_in"))
      (node (ref "J7") (pin "CG4") (pinfunction "CG4_CG4") (pintype "power_in"))
      (node (ref "J7") (pin "CG5") (pinfunction "CG5_CG5") (pintype "power_in"))
      (node (ref "J7") (pin "CG6") (pinfunction "CG6_CG6") (pintype "power_in"))
      (node (ref "J7") (pin "CG7") (pinfunction "CG7_CG7") (pintype "power_in"))
      (node (ref "J7") (pin "CG8") (pinfunction "CG8_CG8") (pintype "power_in"))
      (node (ref "J7") (pin "CG9") (pinfunction "CG9_CG9") (pintype "power_in"))
      (node (ref "J7") (pin "CGND") (pinfunction "CGND_CGND") (pintype "power_in"))
      (node (ref "J7") (pin "D1") (pinfunction "D1_D1") (pintype "bidirectional"))
      (node (ref "J7") (pin "D10") (pinfunction "D10_D10") (pintype "bidirectional"))
      (node (ref "J7") (pin "D13") (pinfunction "D13_D13") (pintype "bidirectional"))
      (node (ref "J7") (pin "D14") (pinfunction "D14_D14") (pintype "bidirectional"))
      (node (ref "J7") (pin "D2") (pinfunction "D2_D2") (pintype "bidirectional"))
      (node (ref "J7") (pin "D25") (pinfunction "D25_D25") (pintype "bidirectional"))
      (node (ref "J7") (pin "D26") (pinfunction "D26_D26") (pintype "bidirectional"))
      (node (ref "J7") (pin "D29") (pinfunction "D29_D29") (pintype "bidirectional"))
      (node (ref "J7") (pin "D30") (pinfunction "D30_D30") (pintype "bidirectional"))
      (node (ref "J7") (pin "D5") (pinfunction "D5_D5") (pintype "bidirectional"))
      (node (ref "J7") (pin "D6") (pinfunction "D6_D6") (pintype "bidirectional"))
      (node (ref "J7") (pin "D9") (pinfunction "D9_D9") (pintype "bidirectional"))
      (node (ref "J7") (pin "DG1") (pinfunction "DG1_DG1") (pintype "power_in"))
      (node (ref "J7") (pin "DG10") (pinfunction "DG10_DG10") (pintype "power_in"))
      (node (ref "J7") (pin "DG11") (pinfunction "DG11_DG11") (pintype "power_in"))
      (node (ref "J7") (pin "DG12") (pinfunction "DG12_DG12") (pintype "power_in"))
      (node (ref "J7") (pin "DG13") (pinfunction "DG13_DG13") (pintype "power_in"))
      (node (ref "J7") (pin "DG14") (pinfunction "DG14_DG14") (pintype "power_in"))
      (node (ref "J7") (pin "DG15") (pinfunction "DG15_DG15") (pintype "power_in"))
      (node (ref "J7") (pin "DG16") (pinfunction "DG16_DG16") (pintype "power_in"))
      (node (ref "J7") (pin "DG17") (pinfunction "DG17_DG17") (pintype "power_in"))
      (node (ref "J7") (pin "DG18") (pinfunction "DG18_DG18") (pintype "power_in"))
      (node (ref "J7") (pin "DG19") (pinfunction "DG19_DG19") (pintype "power_in"))
      (node (ref "J7") (pin "DG2") (pinfunction "DG2_DG2") (pintype "power_in"))
      (node (ref "J7") (pin "DG20") (pinfunction "DG20_DG20") (pintype "power_in"))
      (node (ref "J7") (pin "DG3") (pinfunction "DG3_DG3") (pintype "power_in"))
      (node (ref "J7") (pin "DG4") (pinfunction "DG4_DG4") (pintype "power_in"))
      (node (ref "J7") (pin "DG5") (pinfunction "DG5_DG5") (pintype "power_in"))
      (node (ref "J7") (pin "DG6") (pinfunction "DG6_DG6") (pintype "power_in"))
      (node (ref "J7") (pin "DG7") (pinfunction "DG7_DG7") (pintype "power_in"))
      (node (ref "J7") (pin "DG8") (pinfunction "DG8_DG8") (pintype "power_in"))
      (node (ref "J7") (pin "DG9") (pinfunction "DG9_DG9") (pintype "power_in"))
      (node (ref "J7") (pin "DGND") (pinfunction "DGND_DGND") (pintype "power_in"))
      (node (ref "J8") (pin "AG1") (pinfunction "AG1_AG1") (pintype "power_in"))
      (node (ref "J8") (pin "AG10") (pinfunction "AG10_AG10") (pintype "power_in"))
      (node (ref "J8") (pin "AG11") (pinfunction "AG11_AG11") (pintype "power_in"))
      (node (ref "J8") (pin "AG12") (pinfunction "AG12_AG12") (pintype "power_in"))
      (node (ref "J8") (pin "AG13") (pinfunction "AG13_AG13") (pintype "power_in"))
      (node (ref "J8") (pin "AG14") (pinfunction "AG14_AG14") (pintype "power_in"))
      (node (ref "J8") (pin "AG15") (pinfunction "AG15_AG15") (pintype "power_in"))
      (node (ref "J8") (pin "AG16") (pinfunction "AG16_AG16") (pintype "power_in"))
      (node (ref "J8") (pin "AG17") (pinfunction "AG17_AG17") (pintype "power_in"))
      (node (ref "J8") (pin "AG18") (pinfunction "AG18_AG18") (pintype "power_in"))
      (node (ref "J8") (pin "AG19") (pinfunction "AG19_AG19") (pintype "power_in"))
      (node (ref "J8") (pin "AG2") (pinfunction "AG2_AG2") (pintype "power_in"))
      (node (ref "J8") (pin "AG20") (pinfunction "AG20_AG20") (pintype "power_in"))
      (node (ref "J8") (pin "AG3") (pinfunction "AG3_AG3") (pintype "power_in"))
      (node (ref "J8") (pin "AG4") (pinfunction "AG4_AG4") (pintype "power_in"))
      (node (ref "J8") (pin "AG5") (pinfunction "AG5_AG5") (pintype "power_in"))
      (node (ref "J8") (pin "AG6") (pinfunction "AG6_AG6") (pintype "power_in"))
      (node (ref "J8") (pin "AG7") (pinfunction "AG7_AG7") (pintype "power_in"))
      (node (ref "J8") (pin "AG8") (pinfunction "AG8_AG8") (pintype "power_in"))
      (node (ref "J8") (pin "AG9") (pinfunction "AG9_AG9") (pintype "power_in"))
      (node (ref "J8") (pin "AGND") (pinfunction "AGND_AGND") (pintype "power_in"))
      (node (ref "J8") (pin "BG1") (pinfunction "BG1_BG1") (pintype "power_in"))
      (node (ref "J8") (pin "BG10") (pinfunction "BG10_BG10") (pintype "power_in"))
      (node (ref "J8") (pin "BG11") (pinfunction "BG11_BG11") (pintype "power_in"))
      (node (ref "J8") (pin "BG12") (pinfunction "BG12_BG12") (pintype "power_in"))
      (node (ref "J8") (pin "BG13") (pinfunction "BG13_BG13") (pintype "power_in"))
      (node (ref "J8") (pin "BG14") (pinfunction "BG14_BG14") (pintype "power_in"))
      (node (ref "J8") (pin "BG15") (pinfunction "BG15_BG15") (pintype "power_in"))
      (node (ref "J8") (pin "BG16") (pinfunction "BG16_BG16") (pintype "power_in"))
      (node (ref "J8") (pin "BG17") (pinfunction "BG17_BG17") (pintype "power_in"))
      (node (ref "J8") (pin "BG18") (pinfunction "BG18_BG18") (pintype "power_in"))
      (node (ref "J8") (pin "BG19") (pinfunction "BG19_BG19") (pintype "power_in"))
      (node (ref "J8") (pin "BG2") (pinfunction "BG2_BG2") (pintype "power_in"))
      (node (ref "J8") (pin "BG20") (pinfunction "BG20_BG20") (pintype "power_in"))
      (node (ref "J8") (pin "BG3") (pinfunction "BG3_BG3") (pintype "power_in"))
      (node (ref "J8") (pin "BG4") (pinfunction "BG4_BG4") (pintype "power_in"))
      (node (ref "J8") (pin "BG5") (pinfunction "BG5_BG5") (pintype "power_in"))
      (node (ref "J8") (pin "BG6") (pinfunction "BG6_BG6") (pintype "power_in"))
      (node (ref "J8") (pin "BG7") (pinfunction "BG7_BG7") (pintype "power_in"))
      (node (ref "J8") (pin "BG8") (pinfunction "BG8_BG8") (pintype "power_in"))
      (node (ref "J8") (pin "BG9") (pinfunction "BG9_BG9") (pintype "power_in"))
      (node (ref "J8") (pin "BGND") (pinfunction "BGND_BGND") (pintype "power_in"))
      (node (ref "J8") (pin "C1") (pinfunction "C1_C1") (pintype "bidirectional"))
      (node (ref "J8") (pin "C10") (pinfunction "C10_C10") (pintype "bidirectional"))
      (node (ref "J8") (pin "C13") (pinfunction "C13_C13") (pintype "bidirectional"))
      (node (ref "J8") (pin "C14") (pinfunction "C14_C14") (pintype "bidirectional"))
      (node (ref "J8") (pin "C2") (pinfunction "C2_C2") (pintype "bidirectional"))
      (node (ref "J8") (pin "C25") (pinfunction "C25_C25") (pintype "bidirectional"))
      (node (ref "J8") (pin "C26") (pinfunction "C26_C26") (pintype "bidirectional"))
      (node (ref "J8") (pin "C29") (pinfunction "C29_C29") (pintype "bidirectional"))
      (node (ref "J8") (pin "C30") (pinfunction "C30_C30") (pintype "bidirectional"))
      (node (ref "J8") (pin "C5") (pinfunction "C5_C5") (pintype "bidirectional"))
      (node (ref "J8") (pin "C6") (pinfunction "C6_C6") (pintype "bidirectional"))
      (node (ref "J8") (pin "C9") (pinfunction "C9_C9") (pintype "bidirectional"))
      (node (ref "J8") (pin "CG1") (pinfunction "CG1_CG1") (pintype "power_in"))
      (node (ref "J8") (pin "CG10") (pinfunction "CG10_CG10") (pintype "power_in"))
      (node (ref "J8") (pin "CG11") (pinfunction "CG11_CG11") (pintype "power_in"))
      (node (ref "J8") (pin "CG12") (pinfunction "CG12_CG12") (pintype "power_in"))
      (node (ref "J8") (pin "CG13") (pinfunction "CG13_CG13") (pintype "power_in"))
      (node (ref "J8") (pin "CG14") (pinfunction "CG14_CG14") (pintype "power_in"))
      (node (ref "J8") (pin "CG15") (pinfunction "CG15_CG15") (pintype "power_in"))
      (node (ref "J8") (pin "CG16") (pinfunction "CG16_CG16") (pintype "power_in"))
      (node (ref "J8") (pin "CG17") (pinfunction "CG17_CG17") (pintype "power_in"))
      (node (ref "J8") (pin "CG18") (pinfunction "CG18_CG18") (pintype "power_in"))
      (node (ref "J8") (pin "CG19") (pinfunction "CG19_CG19") (pintype "power_in"))
      (node (ref "J8") (pin "CG2") (pinfunction "CG2_CG2") (pintype "power_in"))
      (node (ref "J8") (pin "CG20") (pinfunction "CG20_CG20") (pintype "power_in"))
      (node (ref "J8") (pin "CG3") (pinfunction "CG3_CG3") (pintype "power_in"))
      (node (ref "J8") (pin "CG4") (pinfunction "CG4_CG4") (pintype "power_in"))
      (node (ref "J8") (pin "CG5") (pinfunction "CG5_CG5") (pintype "power_in"))
      (node (ref "J8") (pin "CG6") (pinfunction "CG6_CG6") (pintype "power_in"))
      (node (ref "J8") (pin "CG7") (pinfunction "CG7_CG7") (pintype "power_in"))
      (node (ref "J8") (pin "CG8") (pinfunction "CG8_CG8") (pintype "power_in"))
      (node (ref "J8") (pin "CG9") (pinfunction "CG9_CG9") (pintype "power_in"))
      (node (ref "J8") (pin "CGND") (pinfunction "CGND_CGND") (pintype "power_in"))
      (node (ref "J8") (pin "D1") (pinfunction "D1_D1") (pintype "bidirectional"))
      (node (ref "J8") (pin "D10") (pinfunction "D10_D10") (pintype "bidirectional"))
      (node (ref "J8") (pin "D13") (pinfunction "D13_D13") (pintype "bidirectional"))
      (node (ref "J8") (pin "D14") (pinfunction "D14_D14") (pintype "bidirectional"))
      (node (ref "J8") (pin "D2") (pinfunction "D2_D2") (pintype "bidirectional"))
      (node (ref "J8") (pin "D25") (pinfunction "D25_D25") (pintype "bidirectional"))
      (node (ref "J8") (pin "D26") (pinfunction "D26_D26") (pintype "bidirectional"))
      (node (ref "J8") (pin "D29") (pinfunction "D29_D29") (pintype "bidirectional"))
      (node (ref "J8") (pin "D30") (pinfunction "D30_D30") (pintype "bidirectional"))
      (node (ref "J8") (pin "D5") (pinfunction "D5_D5") (pintype "bidirectional"))
      (node (ref "J8") (pin "D6") (pinfunction "D6_D6") (pintype "bidirectional"))
      (node (ref "J8") (pin "D9") (pinfunction "D9_D9") (pintype "bidirectional"))
      (node (ref "J8") (pin "DG1") (pinfunction "DG1_DG1") (pintype "power_in"))
      (node (ref "J8") (pin "DG10") (pinfunction "DG10_DG10") (pintype "power_in"))
      (node (ref "J8") (pin "DG11") (pinfunction "DG11_DG11") (pintype "power_in"))
      (node (ref "J8") (pin "DG12") (pinfunction "DG12_DG12") (pintype "power_in"))
      (node (ref "J8") (pin "DG13") (pinfunction "DG13_DG13") (pintype "power_in"))
      (node (ref "J8") (pin "DG14") (pinfunction "DG14_DG14") (pintype "power_in"))
      (node (ref "J8") (pin "DG15") (pinfunction "DG15_DG15") (pintype "power_in"))
      (node (ref "J8") (pin "DG16") (pinfunction "DG16_DG16") (pintype "power_in"))
      (node (ref "J8") (pin "DG17") (pinfunction "DG17_DG17") (pintype "power_in"))
      (node (ref "J8") (pin "DG18") (pinfunction "DG18_DG18") (pintype "power_in"))
      (node (ref "J8") (pin "DG19") (pinfunction "DG19_DG19") (pintype "power_in"))
      (node (ref "J8") (pin "DG2") (pinfunction "DG2_DG2") (pintype "power_in"))
      (node (ref "J8") (pin "DG20") (pinfunction "DG20_DG20") (pintype "power_in"))
      (node (ref "J8") (pin "DG3") (pinfunction "DG3_DG3") (pintype "power_in"))
      (node (ref "J8") (pin "DG4") (pinfunction "DG4_DG4") (pintype "power_in"))
      (node (ref "J8") (pin "DG5") (pinfunction "DG5_DG5") (pintype "power_in"))
      (node (ref "J8") (pin "DG6") (pinfunction "DG6_DG6") (pintype "power_in"))
      (node (ref "J8") (pin "DG7") (pinfunction "DG7_DG7") (pintype "power_in"))
      (node (ref "J8") (pin "DG8") (pinfunction "DG8_DG8") (pintype "power_in"))
      (node (ref "J8") (pin "DG9") (pinfunction "DG9_DG9") (pintype "power_in"))
      (node (ref "J8") (pin "DGND") (pinfunction "DGND_DGND") (pintype "power_in"))
      (node (ref "Q16") (pin "2") (pinfunction "S_2") (pintype "passive"))
      (node (ref "Q4") (pin "2") (pinfunction "S_2") (pintype "passive"))
      (node (ref "U32") (pin "13") (pinfunction "GND_13") (pintype "power_in"))
      (node (ref "U32") (pin "17") (pinfunction "GND_17") (pintype "power_in"))
      (node (ref "U84") (pin "13") (pinfunction "GND_13") (pintype "power_in"))
      (node (ref "U84") (pin "17") (pinfunction "GND_17") (pintype "power_in"))
    )
    (net (code "172") (name "Net-(C181-Pad2)") (class "Default")
      (node (ref "C181") (pin "2") (pinfunction "2_2") (pintype "passive"))
      (node (ref "C751") (pin "2") (pinfunction "2_2") (pintype "passive"))
      (node (ref "C752") (pin "2") (pinfunction "2_2") (pintype "passive"))
      (node (ref "C753") (pin "2") (pinfunction "2_2") (pintype "passive"))
      (node (ref "L25") (pin "1") (pinfunction "1_1") (pintype "passive"))
      (node (ref "U32") (pin "14") (pinfunction "VCC_14") (pintype "power_in"))
      (node (ref "U32") (pin "7") (pinfunction "VCC_7") (pintype "power_in"))
    )
    (net (code "173") (name "Net-(C762-Pad2)") (class "Default")
      (node (ref "C762") (pin "2") (pinfunction "2_2") (pintype "passive"))
      (node (ref "C763") (pin "2") (pinfunction "2_2") (pintype "passive"))
      (node (ref "C764") (pin "2") (pinfunction "2_2") (pintype "passive"))
      (node (ref "C765") (pin "2") (pinfunction "2_2") (pintype "passive"))
      (node (ref "L26") (pin "1") (pinfunction "1_1") (pintype "passive"))
      (node (ref "U84") (pin "14") (pinfunction "VCC_14") (pintype "power_in"))
      (node (ref "U84") (pin "7") (pinfunction "VCC_7") (pintype "power_in"))
    )
    (net (code "174") (name "Net-(Q4-D)") (class "Default")
      (node (ref "Q4") (pin "3") (pinfunction "D_3") (pintype "passive"))
      (node (ref "U32") (pin "8") (pinfunction "EN_8") (pintype "input"))
    )
    (net (code "175") (name "Net-(Q4-G)") (class "Default")
      (node (ref "J7") (pin "D17") (pinfunction "D17_D17") (pintype "bidirectional"))
      (node (ref "Q4") (pin "1") (pinfunction "G_1") (pintype "passive"))
      (node (ref "R493") (pin "2") (pinfunction "2_2") (pintype "passive"))
    )
    (net (code "176") (name "Net-(Q16-D)") (class "Default")
      (node (ref "Q16") (pin "3") (pinfunction "D_3") (pintype "passive"))
      (node (ref "U84") (pin "8") (pinfunction "EN_8") (pintype "input"))
    )
    (net (code "177") (name "Net-(Q16-G)") (class "Default")
      (node (ref "J8") (pin "D17") (pinfunction "D17_D17") (pintype "bidirectional"))
      (node (ref "Q16") (pin "1") (pinfunction "G_1") (pintype "passive"))
      (node (ref "R494") (pin "2") (pinfunction "2_2") (pintype "passive"))
    )
    (net (code "178") (name "Net-(U32-Q0)") (class "Default")
      (node (ref "C754") (pin "1") (pinfunction "1_1") (pintype "passive"))
      (node (ref "U32") (pin "15") (pinfunction "Q0_15") (pintype "output"))
    )
    (net (code "179") (name "Net-(U32-Q0n)") (class "Default")
      (node (ref "C755") (pin "1") (pinfunction "1_1") (pintype "passive"))
      (node (ref "U32") (pin "16") (pinfunction "Q0n_16") (pintype "output"))
    )
    (net (code "180") (name "Net-(U32-Q1)") (class "Default")
      (node (ref "C756") (pin "1") (pinfunction "1_1") (pintype "passive"))
      (node (ref "U32") (pin "1") (pinfunction "Q1_1") (pintype "output"))
    )
    (net (code "181") (name "Net-(U32-Q1n)") (class "Default")
      (node (ref "C757") (pin "1") (pinfunction "1_1") (pintype "passive"))
      (node (ref "U32") (pin "2") (pinfunction "Q1n_2") (pintype "output"))
    )
    (net (code "182") (name "Net-(U32-Q2)") (class "Default")
      (node (ref "C758") (pin "1") (pinfunction "1_1") (pintype "passive"))
      (node (ref "U32") (pin "3") (pinfunction "Q2_3") (pintype "output"))
    )
    (net (code "183") (name "Net-(U32-Q2n)") (class "Default")
      (node (ref "C759") (pin "1") (pinfunction "1_1") (pintype "passive"))
      (node (ref "U32") (pin "4") (pinfunction "Q2n_4") (pintype "output"))
    )
    (net (code "184") (name "Net-(U32-Q3)") (class "Default")
      (node (ref "C760") (pin "1") (pinfunction "1_1") (pintype "passive"))
      (node (ref "U32") (pin "5") (pinfunction "Q3_5") (pintype "output"))
    )
    (net (code "185") (name "Net-(U32-Q3n)") (class "Default")
      (node (ref "C761") (pin "1") (pinfunction "1_1") (pintype "passive"))
      (node (ref "U32") (pin "6") (pinfunction "Q3n_6") (pintype "output"))
    )
    (net (code "186") (name "Net-(U84-Q0)") (class "Default")
      (node (ref "C766") (pin "1") (pinfunction "1_1") (pintype "passive"))
      (node (ref "U84") (pin "15") (pinfunction "Q0_15") (pintype "output"))
    )
    (net (code "187") (name "Net-(U84-Q0n)") (class "Default")
      (node (ref "C767") (pin "1") (pinfunction "1_1") (pintype "passive"))
      (node (ref "U84") (pin "16") (pinfunction "Q0n_16") (pintype "output"))
    )
    (net (code "188") (name "Net-(U84-Q1)") (class "Default")
      (node (ref "C768") (pin "1") (pinfunction "1_1") (pintype "passive"))
      (node (ref "U84") (pin "1") (pinfunction "Q1_1") (pintype "output"))
    )
    (net (code "189") (name "Net-(U84-Q1n)") (class "Default")
      (node (ref "C769") (pin "1") (pinfunction "1_1") (pintype "passive"))
      (node (ref "U84") (pin "2") (pinfunction "Q1n_2") (pintype "output"))
    )
    (net (code "190") (name "Net-(U84-Q2)") (class "Default")
      (node (ref "C770") (pin "1") (pinfunction "1_1") (pintype "passive"))
      (node (ref "U84") (pin "3") (pinfunction "Q2_3") (pintype "output"))
    )
    (net (code "191") (name "Net-(U84-Q2n)") (class "Default")
      (node (ref "C771") (pin "1") (pinfunction "1_1") (pintype "passive"))
      (node (ref "U84") (pin "4") (pinfunction "Q2n_4") (pintype "output"))
    )
    (net (code "192") (name "Net-(U84-Q3)") (class "Default")
      (node (ref "C772") (pin "1") (pinfunction "1_1") (pintype "passive"))
      (node (ref "U84") (pin "5") (pinfunction "Q3_5") (pintype "output"))
    )
    (net (code "193") (name "Net-(U84-Q3n)") (class "Default")
      (node (ref "C773") (pin "1") (pinfunction "1_1") (pintype "passive"))
      (node (ref "U84") (pin "6") (pinfunction "Q3n_6") (pintype "output"))
    )
    (net (code "194") (name "unconnected-(J7-PadC23)") (class "Default")
      (node (ref "J7") (pin "C23") (pinfunction "C23_C23") (pintype "bidirectional+no_connect"))
    )
    (net (code "195") (name "unconnected-(J7-PadC24)") (class "Default")
      (node (ref "J7") (pin "C24") (pinfunction "C24_C24") (pintype "bidirectional+no_connect"))
    )
    (net (code "196") (name "unconnected-(J7-PadD18)") (class "Default")
      (node (ref "J7") (pin "D18") (pinfunction "D18_D18") (pintype "bidirectional+no_connect"))
    )
    (net (code "197") (name "unconnected-(J7-PadD19)") (class "Default")
      (node (ref "J7") (pin "D19") (pinfunction "D19_D19") (pintype "bidirectional+no_connect"))
    )
    (net (code "198") (name "unconnected-(J7-PadD20)") (class "Default")
      (node (ref "J7") (pin "D20") (pinfunction "D20_D20") (pintype "bidirectional+no_connect"))
    )
    (net (code "199") (name "unconnected-(J7-PadD21)") (class "Default")
      (node (ref "J7") (pin "D21") (pinfunction "D21_D21") (pintype "bidirectional+no_connect"))
    )
    (net (code "200") (name "unconnected-(J7-PadD22)") (class "Default")
      (node (ref "J7") (pin "D22") (pinfunction "D22_D22") (pintype "bidirectional+no_connect"))
    )
    (net (code "201") (name "unconnected-(J8-PadC23)") (class "Default")
      (node (ref "J8") (pin "C23") (pinfunction "C23_C23") (pintype "bidirectional+no_connect"))
    )
    (net (code "202") (name "unconnected-(J8-PadC24)") (class "Default")
      (node (ref "J8") (pin "C24") (pinfunction "C24_C24") (pintype "bidirectional+no_connect"))
    )
    (net (code "203") (name "unconnected-(J8-PadD18)") (class "Default")
      (node (ref "J8") (pin "D18") (pinfunction "D18_D18") (pintype "bidirectional+no_connect"))
    )
    (net (code "204") (name "unconnected-(J8-PadD19)") (class "Default")
      (node (ref "J8") (pin "D19") (pinfunction "D19_D19") (pintype "bidirectional+no_connect"))
    )
    (net (code "205") (name "unconnected-(J8-PadD20)") (class "Default")
      (node (ref "J8") (pin "D20") (pinfunction "D20_D20") (pintype "bidirectional+no_connect"))
    )
    (net (code "206") (name "unconnected-(J8-PadD21)") (class "Default")
      (node (ref "J8") (pin "D21") (pinfunction "D21_D21") (pintype "bidirectional+no_connect"))
    )
    (net (code "207") (name "unconnected-(J8-PadD22)") (class "Default")
      (node (ref "J8") (pin "D22") (pinfunction "D22_D22") (pintype "bidirectional+no_connect"))
    )
    (net (code "208") (name "unconnected-(U32-VREF-AC-Pad10)") (class "Default")
      (node (ref "U32") (pin "10") (pinfunction "VREF-AC_10") (pintype "power_in+no_connect"))
    )
    (net (code "209") (name "unconnected-(U32-VT-Pad11)") (class "Default")
      (node (ref "U32") (pin "11") (pinfunction "VT_11") (pintype "power_in+no_connect"))
    )
    (net (code "210") (name "unconnected-(U84-VREF-AC-Pad10)") (class "Default")
      (node (ref "U84") (pin "10") (pinfunction "VREF-AC_10") (pintype "power_in+no_connect"))
    )
    (net (code "211") (name "unconnected-(U84-VT-Pad11)") (class "Default")
      (node (ref "U84") (pin "11") (pinfunction "VT_11") (pintype "power_in+no_connect"))
    )
  )
)
